# td1208-breakout3V3_v1_1.net
KiCad netlist of a schematic drawn in EAGLE
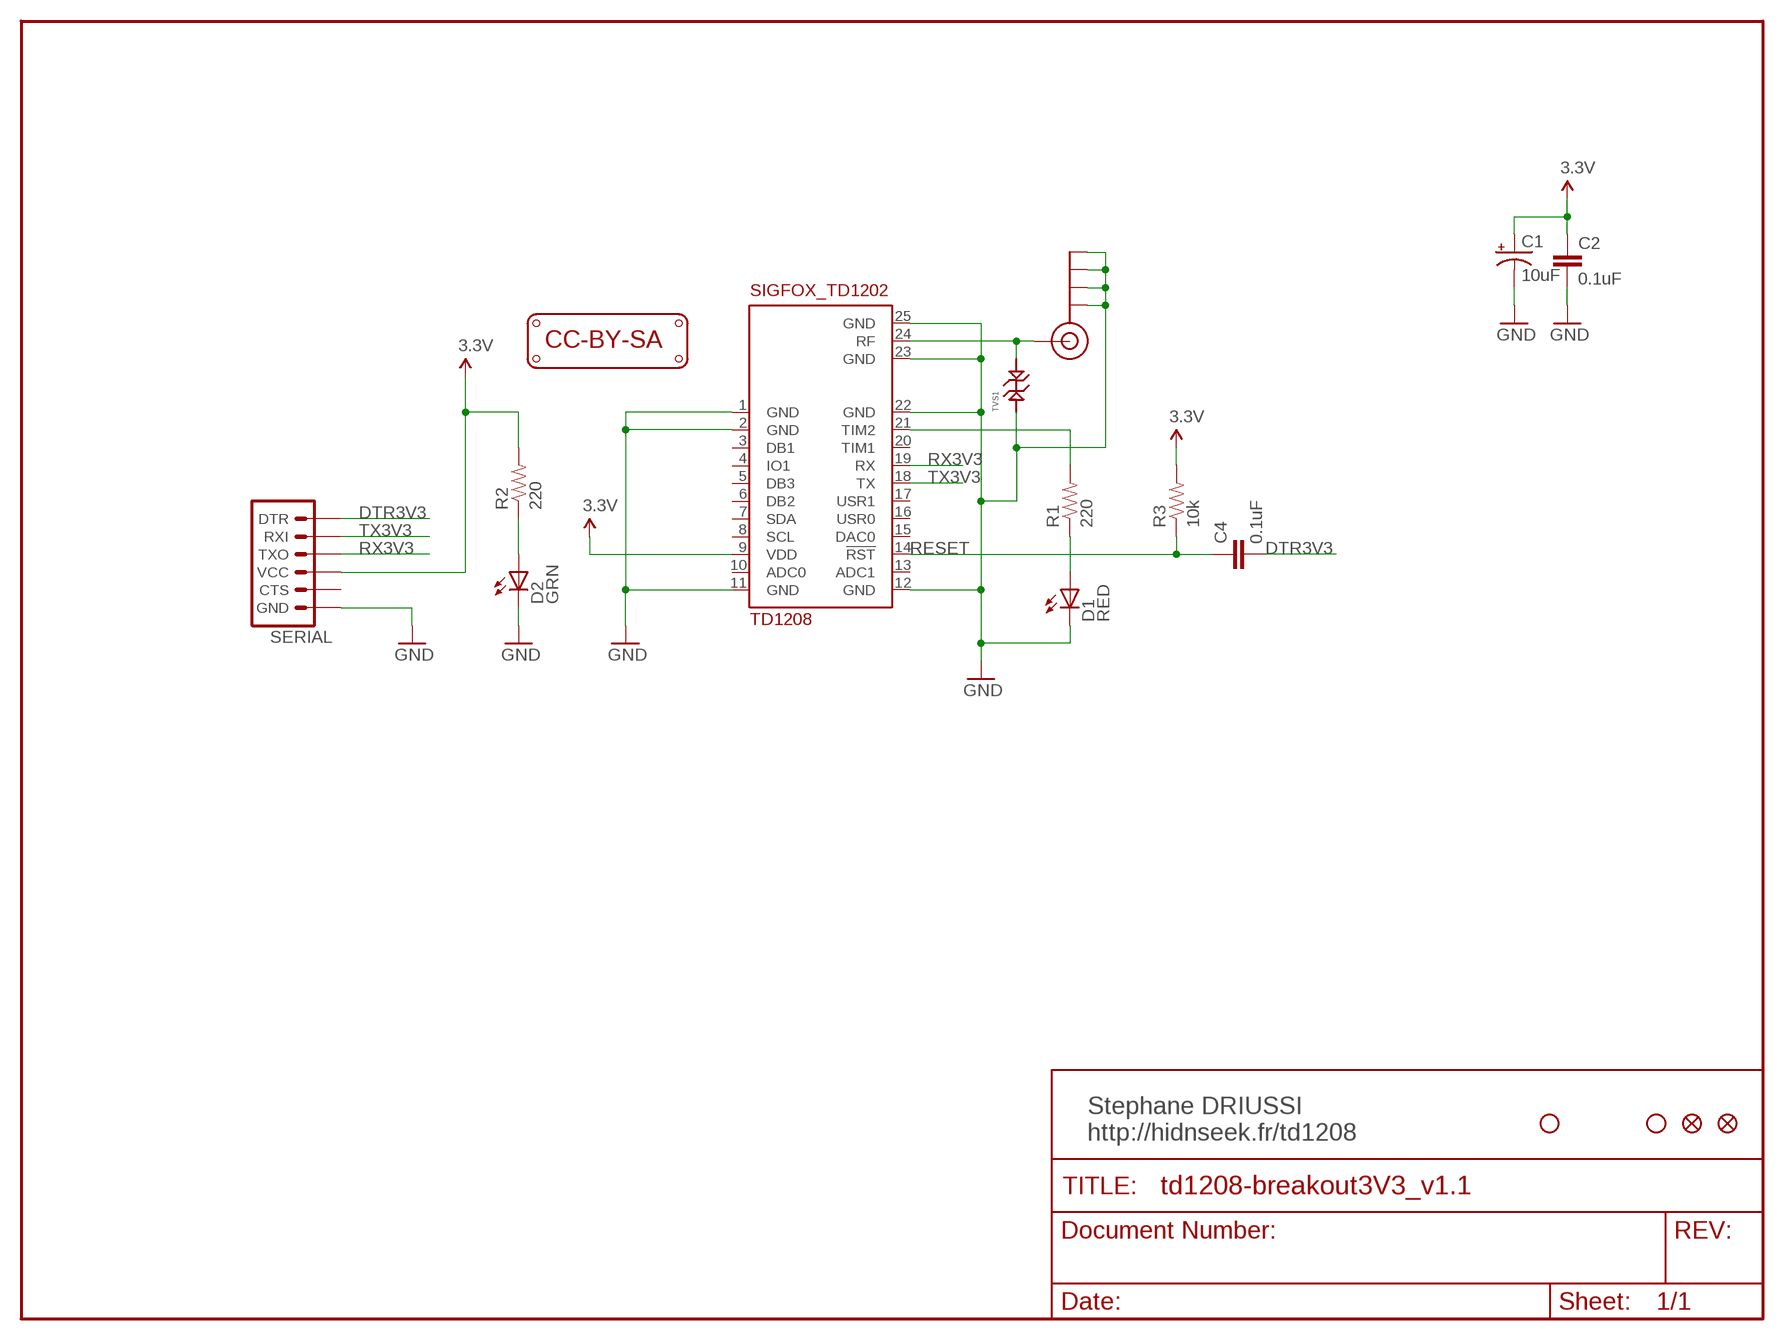
[diagram p0: schematic, sheet 1]

(export (version "E")
  (design (tool "Eeschema 10.0.6"))
  (components
    (comp (ref "C1")
      (value "10uF")
      (footprint "eagle-import:EIA3216")
      (libsource (lib "eagle-import") (part "CAP_POL1206"))
    )
    (comp (ref "C2")
      (value "0.1uF")
      (footprint "eagle-import:0402-CAP")
      (libsource (lib "eagle-import") (part "CAP0402-CAP"))
    )
    (comp (ref "C4")
      (value "0.1uF")
      (footprint "eagle-import:0402-CAP")
      (libsource (lib "eagle-import") (part "CAP0402-CAP"))
    )
    (comp (ref "D1")
      (value "RED")
      (footprint "eagle-import:CHIP-LED0603")
      (libsource (lib "eagle-import") (part "LEDCHIP-LED0603"))
    )
    (comp (ref "D2")
      (value "GRN")
      (footprint "eagle-import:CHIP-LED0603")
      (libsource (lib "eagle-import") (part "LEDCHIP-LED0603"))
    )
    (comp (ref "J$1")
      (value "SMA_EDGE")
      (footprint "eagle-import:SMA_EDGE")
      (libsource (lib "eagle-import") (part "SMA_EDGE"))
    )
    (comp (ref "LOGO1")
      (value "LOGO_CC-BY-SA")
      (footprint "eagle-import:LOGO_CC-BY-SA")
      (libsource (lib "eagle-import") (part "LOGO_CC-BY-SA"))
    )
    (comp (ref "R1")
      (value "220")
      (footprint "eagle-import:0402-RES")
      (libsource (lib "eagle-import") (part "RESISTOR0402-RES"))
    )
    (comp (ref "R2")
      (value "220")
      (footprint "eagle-import:0402-RES")
      (libsource (lib "eagle-import") (part "RESISTOR0402-RES"))
    )
    (comp (ref "R3")
      (value "10k")
      (footprint "eagle-import:0402-RES")
      (libsource (lib "eagle-import") (part "RESISTOR0402-RES"))
    )
    (comp (ref "SERIAL")
      (value "ARDUINO_SERIAL_PROGRAMPTH")
      (footprint "eagle-import:1X06")
      (libsource (lib "eagle-import") (part "ARDUINO_SERIAL_PROGRAMPTH"))
    )
    (comp (ref "TD1208")
      (value "SIGFOX_TD1202")
      (footprint "eagle-import:TD1202")
      (libsource (lib "eagle-import") (part "SIGFOX_TD1202"))
    )
    (comp (ref "TVS1")
      (value "TVS_DIODESOD-923")
      (footprint "eagle-import:SOD-923")
      (libsource (lib "eagle-import") (part "TVS_DIODESOD-923"))
    )
    (comp (ref "U$5")
      (value "STAND-OFF")
      (footprint "eagle-import:STAND-OFF")
      (libsource (lib "eagle-import") (part "STAND-OFF"))
    )
    (comp (ref "U$7")
      (value "FIDUCIAL1X2")
      (footprint "eagle-import:FIDUCIAL-1X2")
      (libsource (lib "eagle-import") (part "FIDUCIAL1X2"))
    )
    (comp (ref "U$11")
      (value "STAND-OFF")
      (footprint "eagle-import:STAND-OFF")
      (libsource (lib "eagle-import") (part "STAND-OFF"))
    )
    (comp (ref "U$16")
      (value "FIDUCIAL1X2")
      (footprint "eagle-import:FIDUCIAL-1X2")
      (libsource (lib "eagle-import") (part "FIDUCIAL1X2"))
    )
  )
  (nets
    (net (code "1") (name "/DTR3V3") (class "Default")
      (node (ref "C4") (pin "2") (pinfunction "2_2") (pintype "passive"))
      (node (ref "SERIAL") (pin "1") (pinfunction "DTR_1") (pintype "passive"))
    )
    (net (code "2") (name "/RESET") (class "Default")
      (node (ref "C4") (pin "1") (pinfunction "1_1") (pintype "passive"))
      (node (ref "R3") (pin "1") (pinfunction "1_1") (pintype "passive"))
      (node (ref "TD1208") (pin "14") (pinfunction "~{RST}_14") (pintype "input"))
    )
    (net (code "3") (name "/RX3V3") (class "Default")
      (node (ref "SERIAL") (pin "3") (pinfunction "TXO_3") (pintype "passive"))
      (node (ref "TD1208") (pin "19") (pinfunction "RX_19") (pintype "input"))
    )
    (net (code "4") (name "/TX3V3") (class "Default")
      (node (ref "SERIAL") (pin "2") (pinfunction "RXI_2") (pintype "passive"))
      (node (ref "TD1208") (pin "18") (pinfunction "TX_18") (pintype "output"))
    )
    (net (code "5") (name "3.3V") (class "Default")
      (node (ref "C1") (pin "A") (pinfunction "+_A") (pintype "passive"))
      (node (ref "C2") (pin "1") (pinfunction "1_1") (pintype "passive"))
      (node (ref "R2") (pin "2") (pinfunction "2_2") (pintype "passive"))
      (node (ref "R3") (pin "2") (pinfunction "2_2") (pintype "passive"))
      (node (ref "SERIAL") (pin "4") (pinfunction "VCC_4") (pintype "passive"))
      (node (ref "TD1208") (pin "9") (pinfunction "VDD_9") (pintype "power_in"))
    )
    (net (code "6") (name "GND") (class "Default")
      (node (ref "C1") (pin "C") (pinfunction "-_C") (pintype "passive"))
      (node (ref "C2") (pin "2") (pinfunction "2_2") (pintype "passive"))
      (node (ref "D1") (pin "C") (pinfunction "C_C") (pintype "passive"))
      (node (ref "D2") (pin "C") (pinfunction "C_C") (pintype "passive"))
      (node (ref "J$1") (pin "GND@0") (pinfunction "GND_GND@0") (pintype "bidirectional"))
      (node (ref "J$1") (pin "GND@1") (pinfunction "GND_GND@1") (pintype "bidirectional"))
      (node (ref "J$1") (pin "GND@2") (pinfunction "GND_GND@2") (pintype "bidirectional"))
      (node (ref "J$1") (pin "GND@3") (pinfunction "GND_GND@3") (pintype "bidirectional"))
      (node (ref "SERIAL") (pin "6") (pinfunction "GND_6") (pintype "passive"))
      (node (ref "TD1208") (pin "1") (pinfunction "GND_1") (pintype "power_in"))
      (node (ref "TD1208") (pin "11") (pinfunction "GND_11") (pintype "power_in"))
      (node (ref "TD1208") (pin "12") (pinfunction "GND_12") (pintype "bidirectional"))
      (node (ref "TD1208") (pin "2") (pinfunction "GND_2") (pintype "power_in"))
      (node (ref "TD1208") (pin "22") (pinfunction "GND_22") (pintype "bidirectional"))
      (node (ref "TD1208") (pin "23") (pinfunction "GND_23") (pintype "bidirectional"))
      (node (ref "TD1208") (pin "25") (pinfunction "GND_25") (pintype "bidirectional"))
      (node (ref "TVS1") (pin "P$1") (pinfunction "P$1_P$1") (pintype "bidirectional"))
    )
    (net (code "7") (name "Net-(D1-PadA)") (class "Default")
      (node (ref "D1") (pin "A") (pinfunction "A_A") (pintype "passive"))
      (node (ref "R1") (pin "1") (pinfunction "1_1") (pintype "passive"))
    )
    (net (code "8") (name "Net-(D2-PadA)") (class "Default")
      (node (ref "D2") (pin "A") (pinfunction "A_A") (pintype "passive"))
      (node (ref "R2") (pin "1") (pinfunction "1_1") (pintype "passive"))
    )
    (net (code "9") (name "Net-(J$1-SIGNAL)") (class "Default")
      (node (ref "J$1") (pin "SIG") (pinfunction "SIGNAL_SIG") (pintype "bidirectional"))
      (node (ref "TD1208") (pin "24") (pinfunction "RF_24") (pintype "output"))
      (node (ref "TVS1") (pin "P$2") (pinfunction "P$2_P$2") (pintype "bidirectional"))
    )
    (net (code "10") (name "Net-(TD1208-TIM2)") (class "Default")
      (node (ref "R1") (pin "2") (pinfunction "2_2") (pintype "passive"))
      (node (ref "TD1208") (pin "21") (pinfunction "TIM2_21") (pintype "bidirectional"))
    )
    (net (code "11") (name "unconnected-(SERIAL-CTS-Pad5)") (class "Default")
      (node (ref "SERIAL") (pin "5") (pinfunction "CTS_5") (pintype "passive"))
    )
    (net (code "12") (name "unconnected-(TD1208-ADC0-Pad10)") (class "Default")
      (node (ref "TD1208") (pin "10") (pinfunction "ADC0_10") (pintype "bidirectional"))
    )
    (net (code "13") (name "unconnected-(TD1208-ADC1-Pad13)") (class "Default")
      (node (ref "TD1208") (pin "13") (pinfunction "ADC1_13") (pintype "bidirectional"))
    )
    (net (code "14") (name "unconnected-(TD1208-DAC0-Pad15)") (class "Default")
      (node (ref "TD1208") (pin "15") (pinfunction "DAC0_15") (pintype "bidirectional"))
    )
    (net (code "15") (name "unconnected-(TD1208-DB1-Pad3)") (class "Default")
      (node (ref "TD1208") (pin "3") (pinfunction "DB1_3") (pintype "bidirectional"))
    )
    (net (code "16") (name "unconnected-(TD1208-DB2-Pad6)") (class "Default")
      (node (ref "TD1208") (pin "6") (pinfunction "DB2_6") (pintype "bidirectional"))
    )
    (net (code "17") (name "unconnected-(TD1208-DB3-Pad5)") (class "Default")
      (node (ref "TD1208") (pin "5") (pinfunction "DB3_5") (pintype "bidirectional"))
    )
    (net (code "18") (name "unconnected-(TD1208-IO1-Pad4)") (class "Default")
      (node (ref "TD1208") (pin "4") (pinfunction "IO1_4") (pintype "bidirectional"))
    )
    (net (code "19") (name "unconnected-(TD1208-SCL-Pad8)") (class "Default")
      (node (ref "TD1208") (pin "8") (pinfunction "SCL_8") (pintype "bidirectional"))
    )
    (net (code "20") (name "unconnected-(TD1208-SDA-Pad7)") (class "Default")
      (node (ref "TD1208") (pin "7") (pinfunction "SDA_7") (pintype "bidirectional"))
    )
    (net (code "21") (name "unconnected-(TD1208-TIM1-Pad20)") (class "Default")
      (node (ref "TD1208") (pin "20") (pinfunction "TIM1_20") (pintype "bidirectional"))
    )
    (net (code "22") (name "unconnected-(TD1208-USR0-Pad16)") (class "Default")
      (node (ref "TD1208") (pin "16") (pinfunction "USR0_16") (pintype "bidirectional"))
    )
    (net (code "23") (name "unconnected-(TD1208-USR1-Pad17)") (class "Default")
      (node (ref "TD1208") (pin "17") (pinfunction "USR1_17") (pintype "bidirectional"))
    )
  )
)
